# LKS_074DO_0406.net
KiCad netlist of a schematic drawn in Altium Designer
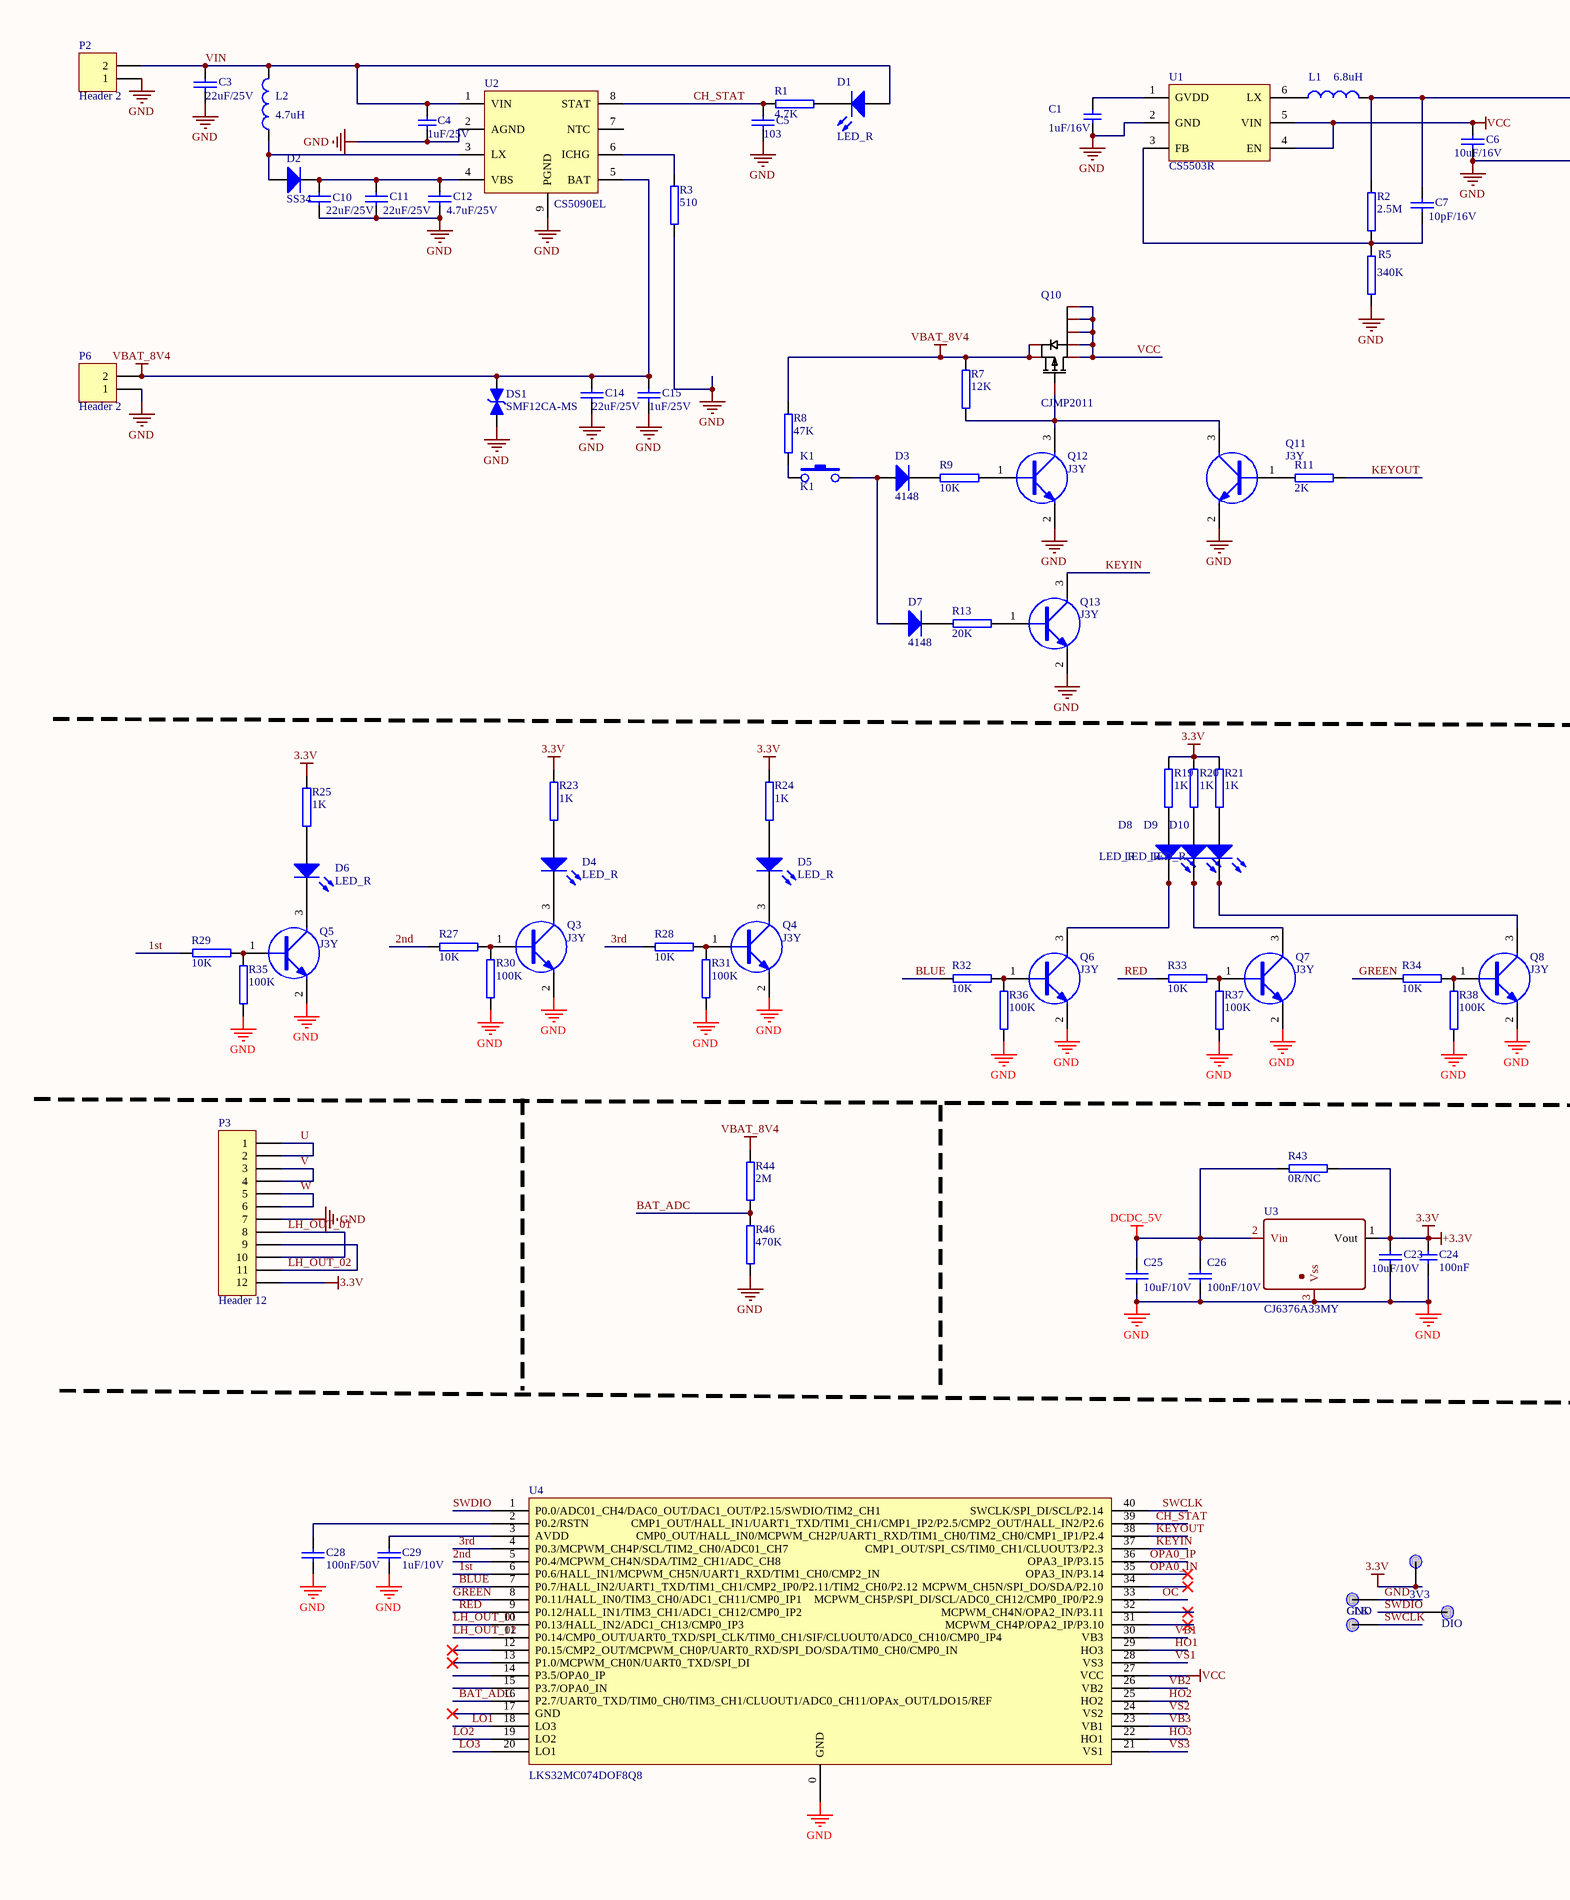
[diagram p0: LKS_074DO_0406.SchDoc, left]
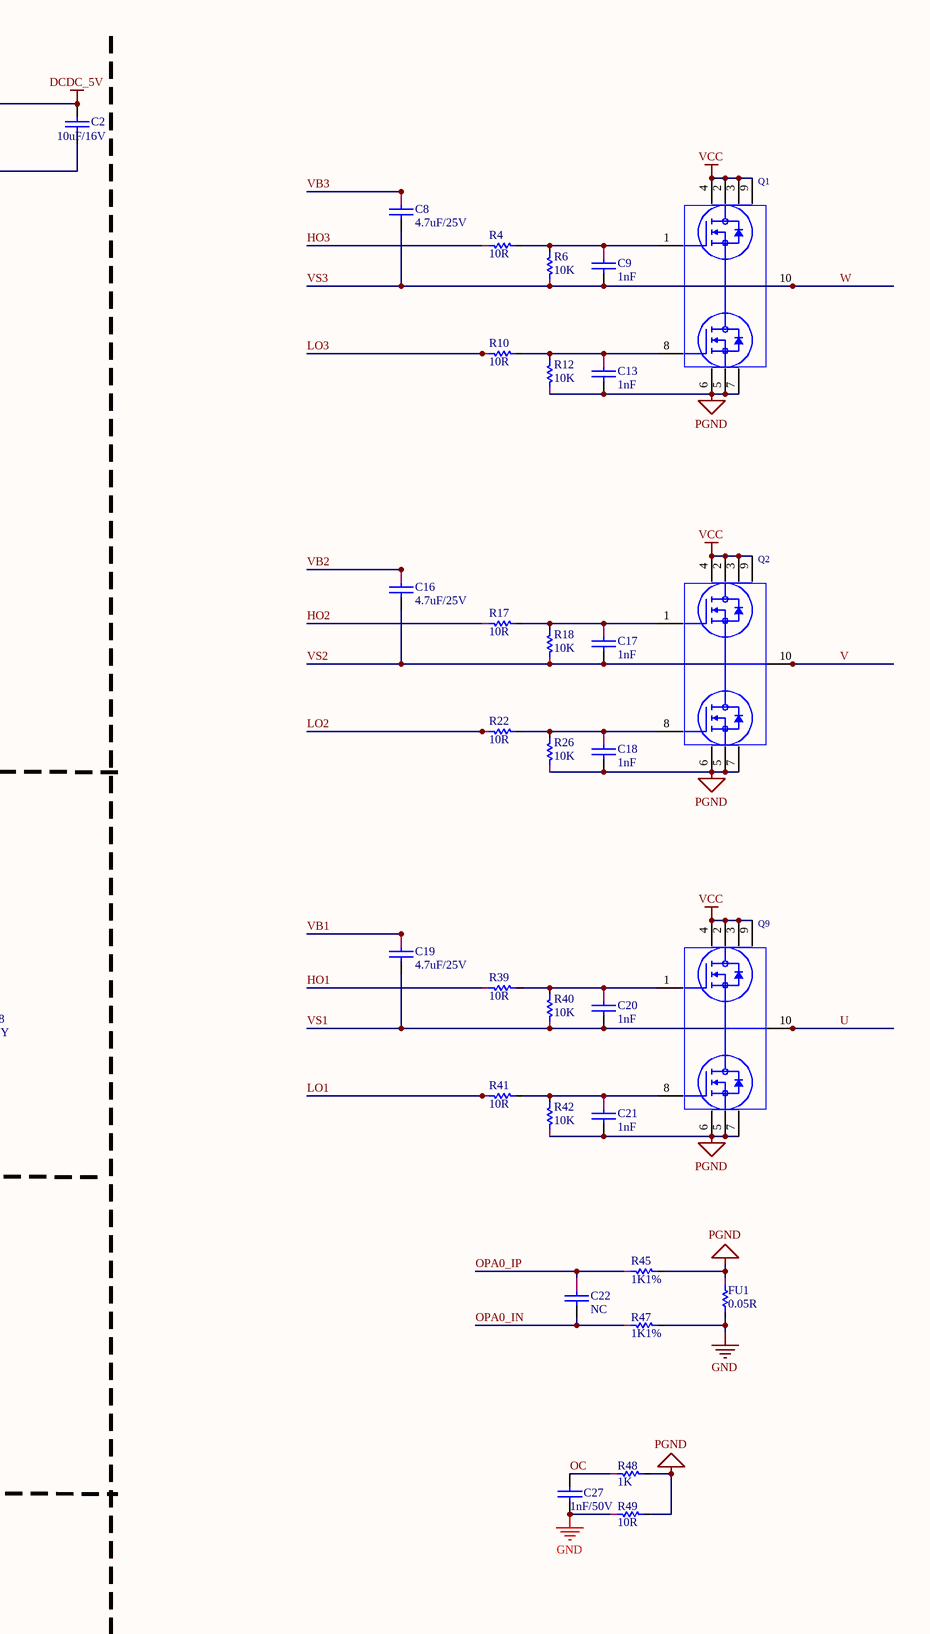
[diagram p1: LKS_074DO_0406.SchDoc, right]

(export (version "E")
  (design (tool "Eeschema 10.0.6"))
  (components
    (comp (ref "3V3") (value "test") (footprint "piot") (libsource (lib "LKS074DO_BRUSH_0329") (part "test")))
    (comp (ref "C1") (value "1uF/16V") (footprint "C 0402_M") (libsource (lib "") (part "CAP_1")))
    (comp (ref "C2")
      (value "10uF/16V")
      (footprint "C 0603_M")
      (description "Capacitor")
      (libsource (lib "*") (part "CAP"))
    )
    (comp (ref "C3")
      (value "22uF/25V")
      (footprint "C 0603_M")
      (description "Capacitor")
      (libsource (lib "*") (part "CAP"))
    )
    (comp (ref "C4") (value "1uF/25V") (footprint "C 0402_M") (libsource (lib "") (part "CAP_1")))
    (comp (ref "C5")
      (value "103")
      (footprint "R 0402_M")
      (description "Capacitor")
      (libsource (lib "*") (part "CAP"))
    )
    (comp (ref "C6")
      (value "10uF/16V")
      (footprint "C 0603_M")
      (description "Capacitor")
      (libsource (lib "*") (part "CAP"))
    )
    (comp (ref "C7")
      (value "10pF/16V")
      (footprint "C 0402_M")
      (description "Capacitor")
      (libsource (lib "*") (part "CAP"))
    )
    (comp (ref "C8")
      (value "4.7uF/25V")
      (footprint "C 0402_M")
      (description "Capacitor")
      (libsource (lib "") (part "CAP_2"))
    )
    (comp (ref "C9")
      (value "1nF")
      (footprint "C 0402_M")
      (description "Capacitor")
      (libsource (lib "") (part "CAP_2"))
    )
    (comp (ref "C10")
      (value "22uF/25V")
      (footprint "C 0603_M")
      (description "Capacitor")
      (libsource (lib "*") (part "CAP"))
    )
    (comp (ref "C11")
      (value "22uF/25V")
      (footprint "C 0603_M")
      (description "Capacitor")
      (libsource (lib "*") (part "CAP"))
    )
    (comp (ref "C12")
      (value "4.7uF/25V")
      (footprint "C 0402_M")
      (description "Capacitor")
      (libsource (lib "*") (part "CAP"))
    )
    (comp (ref "C13")
      (value "1nF")
      (footprint "C 0402_M")
      (description "Capacitor")
      (libsource (lib "") (part "CAP_2"))
    )
    (comp (ref "C14")
      (value "22uF/25V")
      (footprint "C 0603_M")
      (description "Capacitor")
      (libsource (lib "*") (part "CAP"))
    )
    (comp (ref "C15")
      (value "1uF/25V")
      (footprint "C 0402_M")
      (description "Capacitor")
      (libsource (lib "*") (part "CAP"))
    )
    (comp (ref "C16")
      (value "4.7uF/25V")
      (footprint "C 0402_M")
      (description "Capacitor")
      (libsource (lib "") (part "CAP_2"))
    )
    (comp (ref "C17")
      (value "1nF")
      (footprint "C 0402_M")
      (description "Capacitor")
      (libsource (lib "") (part "CAP_2"))
    )
    (comp (ref "C18")
      (value "1nF")
      (footprint "C 0402_M")
      (description "Capacitor")
      (libsource (lib "") (part "CAP_2"))
    )
    (comp (ref "C19")
      (value "4.7uF/25V")
      (footprint "C 0402_M")
      (description "Capacitor")
      (libsource (lib "") (part "CAP_2"))
    )
    (comp (ref "C20")
      (value "1nF")
      (footprint "C 0402_M")
      (description "Capacitor")
      (libsource (lib "") (part "CAP_2"))
    )
    (comp (ref "C21")
      (value "1nF")
      (footprint "C 0402_M")
      (description "Capacitor")
      (libsource (lib "") (part "CAP_2"))
    )
    (comp (ref "C22")
      (value "NC")
      (footprint "C 0402_M")
      (description "Capacitor")
      (libsource (lib "") (part "CAP_2"))
    )
    (comp (ref "C23")
      (value "10uF/10V")
      (footprint "C 0603_M")
      (description "Capacitor")
      (libsource (lib "*") (part "CAP"))
    )
    (comp (ref "C24") (value "100nF") (footprint "C 0402_M") (libsource (lib "") (part "CAP_1")))
    (comp (ref "C25")
      (value "10uF/10V")
      (footprint "C 0603_M")
      (description "Capacitor")
      (libsource (lib "*") (part "CAP"))
    )
    (comp (ref "C26")
      (value "100nF/10V")
      (footprint "C 0402_M")
      (description "Capacitor")
      (libsource (lib "*") (part "CAP"))
    )
    (comp (ref "C27")
      (value "1nF/50V")
      (footprint "C 0402_M")
      (description "Capacitor")
      (libsource (lib "*") (part "C"))
    )
    (comp (ref "C28")
      (value "100nF/50V")
      (footprint "C 0402_M")
      (description "Capacitor")
      (libsource (lib "*") (part "C"))
    )
    (comp (ref "C29")
      (value "1uF/10V")
      (footprint "C 0402_M")
      (description "Capacitor")
      (libsource (lib "*") (part "C"))
    )
    (comp (ref "CLK") (value "test") (footprint "piot") (libsource (lib "LKS074DO_BRUSH_0329") (part "test")))
    (comp (ref "D1") (value "LED_R") (footprint "0603-LED") (libsource (lib "PuXun1") (part "LED")))
    (comp (ref "D2")
      (value "SS34")
      (footprint "SOD123FL")
      (description "Default Diode")
      (fields (field (name "PUBLISHER") "Altium Limited"))
      (libsource (lib "LKS034DO_Motor_0520_1") (part "Diode"))
    )
    (comp (ref "D3")
      (value "4148")
      (footprint "SOD-323")
      (description "Default Diode")
      (fields (field (name "PUBLISHER") "Altium Limited"))
      (libsource (lib "LKS034DO_Motor_0520_1") (part "Diode"))
    )
    (comp (ref "D4") (value "LED_R") (footprint "0603-LED") (libsource (lib "PuXun1") (part "LED")))
    (comp (ref "D5") (value "LED_R") (footprint "0603-LED") (libsource (lib "PuXun1") (part "LED")))
    (comp (ref "D6") (value "LED_R") (footprint "0603-LED") (libsource (lib "PuXun1") (part "LED")))
    (comp (ref "D7")
      (value "4148")
      (footprint "SOD-323")
      (description "Default Diode")
      (fields (field (name "PUBLISHER") "Altium Limited"))
      (libsource (lib "LKS034DO_Motor_0520_1") (part "Diode"))
    )
    (comp (ref "D8") (value "LED_R") (footprint "0603-LED") (libsource (lib "PuXun1") (part "LED")))
    (comp (ref "D9") (value "LED_R") (footprint "0603-LED") (libsource (lib "PuXun1") (part "LED")))
    (comp (ref "D10") (value "LED_R") (footprint "0603-LED") (libsource (lib "PuXun1") (part "LED")))
    (comp (ref "DIO") (value "test") (footprint "piot") (libsource (lib "LKS074DO_BRUSH_0329") (part "test")))
    (comp (ref "DS1")
      (value "SMF12CA-MS")
      (footprint "SOD-123F")
      (description "12V/19.9V")
      (libsource (lib "*") (part "DIODE-3"))
    )
    (comp (ref "FU1") (value "0.05R") (footprint "R 0805_M") (libsource (lib "*") (part "RAS")))
    (comp (ref "GND") (value "test") (footprint "piot") (libsource (lib "LKS074DO_BRUSH_0329") (part "test")))
    (comp (ref "K1") (value "K1") (footprint "SMD3.3X3.3X2") (libsource (lib "SCHLIB_NEW") (part "K1")))
    (comp (ref "L1")
      (value "6.8uH")
      (footprint "SMD3.5X3 .2- duplicate")
      (description "Inductor")
      (fields (field (name "PUBLISHER") "Altium Limited"))
      (libsource (lib "Miscellaneous Devices") (part "Inductor"))
    )
    (comp (ref "L2")
      (value "4.7uH")
      (footprint "SMD3.5X3 .2- duplicate")
      (description "Inductor")
      (fields (field (name "PUBLISHER") "Altium Limited"))
      (libsource (lib "Miscellaneous Devices") (part "Inductor"))
    )
    (comp (ref "P2")
      (value "Header 2")
      (footprint "CONN_SMD_2P_0.6")
      (description "Header, 2-Pin")
      (fields (field (name "PUBLISHER") "Altium Limited"))
      (libsource (lib "Miscellaneous Connectors") (part "Header 2"))
    )
    (comp (ref "P3")
      (value "Header 12")
      (footprint "SMD-12")
      (description "Header, 12-Pin")
      (fields (field (name "PUBLISHER") "Altium Limited"))
      (libsource (lib "Miscellaneous Connectors") (part "Header 12"))
    )
    (comp (ref "P6")
      (value "Header 2")
      (footprint "CONN_SMD_2P_0.6")
      (description "Header, 2-Pin")
      (fields (field (name "PUBLISHER") "Altium Limited"))
      (libsource (lib "Miscellaneous Connectors") (part "Header 2"))
    )
    (comp (ref "Q1") (value "CJBM3020") (footprint "DFN-3X3_8") (libsource (lib "*") (part "CJBM3020")))
    (comp (ref "Q2") (value "CJBM3020") (footprint "DFN-3X3_8") (libsource (lib "*") (part "CJBM3020")))
    (comp (ref "Q3")
      (value "J3Y")
      (footprint "SOT-23")
      (description "NPN Transistor")
      (libsource (lib "*") (part "NPN"))
    )
    (comp (ref "Q4")
      (value "J3Y")
      (footprint "SOT-23")
      (description "NPN Transistor")
      (libsource (lib "*") (part "NPN"))
    )
    (comp (ref "Q5")
      (value "J3Y")
      (footprint "SOT-23")
      (description "NPN Transistor")
      (libsource (lib "*") (part "NPN"))
    )
    (comp (ref "Q6")
      (value "J3Y")
      (footprint "SOT-23")
      (description "NPN Transistor")
      (libsource (lib "*") (part "NPN"))
    )
    (comp (ref "Q7")
      (value "J3Y")
      (footprint "SOT-23")
      (description "NPN Transistor")
      (libsource (lib "*") (part "NPN"))
    )
    (comp (ref "Q8")
      (value "J3Y")
      (footprint "SOT-23")
      (description "NPN Transistor")
      (libsource (lib "*") (part "NPN"))
    )
    (comp (ref "Q9") (value "CJBM3020") (footprint "DFN-3X3_8") (libsource (lib "*") (part "CJBM3020")))
    (comp (ref "Q10")
      (value "CJMP2011")
      (footprint "DFN-6-2X2")
      (libsource (lib "LKS074DO_BRUSH_0329") (part "CJMP2011"))
    )
    (comp (ref "Q11")
      (value "J3Y")
      (footprint "SOT-23")
      (description "NPN Transistor")
      (libsource (lib "*") (part "NPN"))
    )
    (comp (ref "Q12")
      (value "J3Y")
      (footprint "SOT-23")
      (description "NPN Transistor")
      (libsource (lib "*") (part "NPN"))
    )
    (comp (ref "Q13")
      (value "J3Y")
      (footprint "SOT-23")
      (description "NPN Transistor")
      (libsource (lib "*") (part "NPN"))
    )
    (comp (ref "R1") (value "4.7K") (footprint "C 0402_M") (libsource (lib "*") (part "RES2_S")))
    (comp (ref "R2") (value "2.5M") (footprint "C 0402_M") (libsource (lib "*") (part "RES2_S")))
    (comp (ref "R3") (value "510") (footprint "R 0402_M") (libsource (lib "*") (part "RES2_S")))
    (comp (ref "R4") (value "10R") (footprint "R 0402_M") (libsource (lib "*") (part "RAS")))
    (comp (ref "R5") (value "340K") (footprint "C 0402_M") (libsource (lib "*") (part "RES2_S")))
    (comp (ref "R6") (value "10K") (footprint "R 0402_M") (libsource (lib "*") (part "RAS")))
    (comp (ref "R7") (value "12K") (footprint "C 0402_M") (libsource (lib "*") (part "RES2_S")))
    (comp (ref "R8") (value "47K") (footprint "C 0402_M") (libsource (lib "*") (part "RES2_S")))
    (comp (ref "R9") (value "10K") (footprint "C 0402_M") (libsource (lib "*") (part "RES2_S")))
    (comp (ref "R10") (value "10R") (footprint "R 0402_M") (libsource (lib "*") (part "RAS")))
    (comp (ref "R11") (value "2K") (footprint "C 0402_M") (libsource (lib "*") (part "RES2_S")))
    (comp (ref "R12") (value "10K") (footprint "R 0402_M") (libsource (lib "*") (part "RAS")))
    (comp (ref "R13") (value "20K") (footprint "C 0402_M") (libsource (lib "*") (part "RES2_S")))
    (comp (ref "R17") (value "10R") (footprint "R 0402_M") (libsource (lib "*") (part "RAS")))
    (comp (ref "R18") (value "10K") (footprint "R 0402_M") (libsource (lib "*") (part "RAS")))
    (comp (ref "R19") (value "1K") (footprint "C 0402_M") (libsource (lib "*") (part "RES2_S")))
    (comp (ref "R20") (value "1K") (footprint "C 0402_M") (libsource (lib "*") (part "RES2_S")))
    (comp (ref "R21") (value "1K") (footprint "C 0402_M") (libsource (lib "*") (part "RES2_S")))
    (comp (ref "R22") (value "10R") (footprint "R 0402_M") (libsource (lib "*") (part "RAS")))
    (comp (ref "R23") (value "1K") (footprint "C 0402_M") (libsource (lib "*") (part "RES2_S")))
    (comp (ref "R24") (value "1K") (footprint "C 0402_M") (libsource (lib "*") (part "RES2_S")))
    (comp (ref "R25") (value "1K") (footprint "C 0402_M") (libsource (lib "*") (part "RES2_S")))
    (comp (ref "R26") (value "10K") (footprint "R 0402_M") (libsource (lib "*") (part "RAS")))
    (comp (ref "R27") (value "10K") (footprint "C 0402_M") (libsource (lib "*") (part "RES2_S")))
    (comp (ref "R28") (value "10K") (footprint "C 0402_M") (libsource (lib "*") (part "RES2_S")))
    (comp (ref "R29") (value "10K") (footprint "C 0402_M") (libsource (lib "*") (part "RES2_S")))
    (comp (ref "R30") (value "100K") (footprint "C 0402_M") (libsource (lib "*") (part "RES2_S")))
    (comp (ref "R31") (value "100K") (footprint "C 0402_M") (libsource (lib "*") (part "RES2_S")))
    (comp (ref "R32") (value "10K") (footprint "C 0402_M") (libsource (lib "*") (part "RES2_S")))
    (comp (ref "R33") (value "10K") (footprint "C 0402_M") (libsource (lib "*") (part "RES2_S")))
    (comp (ref "R34") (value "10K") (footprint "C 0402_M") (libsource (lib "*") (part "RES2_S")))
    (comp (ref "R35") (value "100K") (footprint "C 0402_M") (libsource (lib "*") (part "RES2_S")))
    (comp (ref "R36") (value "100K") (footprint "C 0402_M") (libsource (lib "*") (part "RES2_S")))
    (comp (ref "R37") (value "100K") (footprint "C 0402_M") (libsource (lib "*") (part "RES2_S")))
    (comp (ref "R38") (value "100K") (footprint "C 0402_M") (libsource (lib "*") (part "RES2_S")))
    (comp (ref "R39") (value "10R") (footprint "R 0402_M") (libsource (lib "*") (part "RAS")))
    (comp (ref "R40") (value "10K") (footprint "R 0402_M") (libsource (lib "*") (part "RAS")))
    (comp (ref "R41") (value "10R") (footprint "R 0402_M") (libsource (lib "*") (part "RAS")))
    (comp (ref "R42") (value "10K") (footprint "R 0402_M") (libsource (lib "*") (part "RAS")))
    (comp (ref "R43") (value "0R/NC") (footprint "0603") (libsource (lib "*") (part "RES2_S")))
    (comp (ref "R44") (value "2M") (footprint "C 0402_M") (libsource (lib "*") (part "RES2_S")))
    (comp (ref "R45") (value "1K1%") (footprint "R 0402_M") (libsource (lib "*") (part "RAS")))
    (comp (ref "R46") (value "470K") (footprint "C 0402_M") (libsource (lib "*") (part "RES2_S")))
    (comp (ref "R47") (value "1K1%") (footprint "R 0402_M") (libsource (lib "*") (part "RAS")))
    (comp (ref "R48") (value "1K") (footprint "R 0402_M") (libsource (lib "*") (part "RAS")))
    (comp (ref "R49") (value "10R") (footprint "R 0402_M") (libsource (lib "*") (part "RAS")))
    (comp (ref "U1")
      (value "CS5503R")
      (footprint "SOT23-6L")
      (libsource (lib "LKS034DO_Motor_0520_1") (part "CS5503R"))
    )
    (comp (ref "U2")
      (value "CS5090EL")
      (footprint "DFN2X2_8_0.5")
      (libsource (lib "LKS034DO_Motor_0520_1") (part "CS5090EL"))
    )
    (comp (ref "U3")
      (value "CJ6376A33MY")
      (footprint "SOT-23")
      (libsource (lib "LKS034DO_Motor_0520_1") (part "78L15"))
    )
    (comp (ref "U4")
      (value "LKS32MC074DOF8Q8")
      (footprint "QFN40")
      (description "芯片")
      (libsource (lib "Q_LINKO_V1.0") (part "LKS32MC074DF8Q8"))
    )
  )
  (nets
    (net (code "1") (name "+3.3V") (class "Default")
      (node (ref "3V3") (pin "1") (pinfunction "1_1") (pintype "passive"))
      (node (ref "C23") (pin "2") (pinfunction "2_2") (pintype "passive"))
      (node (ref "C24") (pin "1") (pinfunction "1_1") (pintype "passive"))
      (node (ref "P3") (pin "12") (pinfunction "12_12") (pintype "passive"))
      (node (ref "R19") (pin "2") (pinfunction "2_2") (pintype "passive"))
      (node (ref "R20") (pin "2") (pinfunction "2_2") (pintype "passive"))
      (node (ref "R21") (pin "2") (pinfunction "2_2") (pintype "passive"))
      (node (ref "R23") (pin "2") (pinfunction "2_2") (pintype "passive"))
      (node (ref "R24") (pin "2") (pinfunction "2_2") (pintype "passive"))
      (node (ref "R25") (pin "2") (pinfunction "2_2") (pintype "passive"))
      (node (ref "R43") (pin "2") (pinfunction "2_2") (pintype "passive"))
      (node (ref "U3") (pin "1") (pinfunction "Vout_1") (pintype "passive"))
    )
    (net (code "2") (name "/1st") (class "Default")
      (node (ref "R29") (pin "2") (pinfunction "2_2") (pintype "passive"))
      (node (ref "U4") (pin "6") (pinfunction "P0.6/HALL_IN1/MCPWM_CH5N/UART1_RXD/TIM1_CH0/CMP2_IN_6") (pintype "passive"))
    )
    (net (code "3") (name "/2nd") (class "Default")
      (node (ref "R27") (pin "2") (pinfunction "2_2") (pintype "passive"))
      (node (ref "U4") (pin "5") (pinfunction "P0.4/MCPWM_CH4N/SDA/TIM2_CH1/ADC_CH8_5") (pintype "passive"))
    )
    (net (code "4") (name "/3rd") (class "Default")
      (node (ref "R28") (pin "2") (pinfunction "2_2") (pintype "passive"))
      (node (ref "U4") (pin "4") (pinfunction "P0.3/MCPWM_CH4P/SCL/TIM2_CH0/ADC01_CH7_4") (pintype "passive"))
    )
    (net (code "5") (name "/BAT_ADC") (class "Default")
      (node (ref "R44") (pin "2") (pinfunction "2_2") (pintype "passive"))
      (node (ref "R46") (pin "1") (pinfunction "1_1") (pintype "passive"))
      (node (ref "U4") (pin "16") (pinfunction "P2.7/UART0_TXD/TIM0_CH0/TIM3_CH1/CLUOUT1/ADC0_CH11/OPAx_OUT/LDO15/REF_16") (pintype "passive"))
    )
    (net (code "6") (name "/BLUE") (class "Default")
      (node (ref "R32") (pin "2") (pinfunction "2_2") (pintype "passive"))
      (node (ref "U4") (pin "7") (pinfunction "P0.7/HALL_IN2/UART1_TXD/TIM1_CH1/CMP2_IP0/P2.11/TIM2_CH0/P2.12_7") (pintype "passive"))
    )
    (net (code "7") (name "/CH_STAT") (class "Default")
      (node (ref "C5") (pin "2") (pinfunction "2_2") (pintype "passive"))
      (node (ref "R1") (pin "1") (pinfunction "1_1") (pintype "passive"))
      (node (ref "U2") (pin "8") (pinfunction "STAT_8") (pintype "passive"))
      (node (ref "U4") (pin "39") (pinfunction "CMP1_OUT/HALL_IN1/UART1_TXD/TIM1_CH1/CMP1_IP2/P2.5/CMP2_OUT/HALL_IN2/P2.6_39") (pintype "passive"))
    )
    (net (code "8") (name "/GREEN") (class "Default")
      (node (ref "R34") (pin "2") (pinfunction "2_2") (pintype "passive"))
      (node (ref "U4") (pin "8") (pinfunction "P0.11/HALL_IN0/TIM3_CH0/ADC1_CH11/CMP0_IP1_8") (pintype "passive"))
    )
    (net (code "9") (name "/HO1") (class "Default")
      (node (ref "R39") (pin "2") (pinfunction "2_2") (pintype "passive"))
      (node (ref "U4") (pin "29") (pinfunction "HO3_29") (pintype "passive"))
    )
    (net (code "10") (name "/HO2") (class "Default")
      (node (ref "R17") (pin "2") (pinfunction "2_2") (pintype "passive"))
      (node (ref "U4") (pin "25") (pinfunction "HO2_25") (pintype "passive"))
    )
    (net (code "11") (name "/HO3") (class "Default")
      (node (ref "R4") (pin "2") (pinfunction "2_2") (pintype "passive"))
      (node (ref "U4") (pin "22") (pinfunction "HO1_22") (pintype "passive"))
    )
    (net (code "12") (name "/KEYIN") (class "Default")
      (node (ref "Q13") (pin "3") (pinfunction "C_3") (pintype "passive"))
      (node (ref "U4") (pin "37") (pinfunction "CMP1_OUT/SPI_CS/TIM0_CH1/CLUOUT3/P2.3_37") (pintype "passive"))
    )
    (net (code "13") (name "/KEYOUT") (class "Default")
      (node (ref "R11") (pin "2") (pinfunction "2_2") (pintype "passive"))
      (node (ref "U4") (pin "38") (pinfunction "CMP0_OUT/HALL_IN0/MCPWM_CH2P/UART1_RXD/TIM1_CH0/TIM2_CH0/CMP1_IP1/P2.4_38") (pintype "passive"))
    )
    (net (code "14") (name "/LH_OUT_01") (class "Default")
      (node (ref "P3") (pin "10") (pinfunction "10_10") (pintype "passive"))
      (node (ref "P3") (pin "8") (pinfunction "8_8") (pintype "passive"))
      (node (ref "U4") (pin "10") (pinfunction "P0.13/HALL_IN2/ADC1_CH13/CMP0_IP3_10") (pintype "passive"))
    )
    (net (code "15") (name "/LH_OUT_02") (class "Default")
      (node (ref "P3") (pin "11") (pinfunction "11_11") (pintype "passive"))
      (node (ref "P3") (pin "9") (pinfunction "9_9") (pintype "passive"))
      (node (ref "U4") (pin "11") (pinfunction "P0.14/CMP0_OUT/UART0_TXD/SPI_CLK/TIM0_CH1/SIF/CLUOUT0/ADC0_CH10/CMP0_IP4_11") (pintype "passive"))
    )
    (net (code "16") (name "/LO1") (class "Default")
      (node (ref "R41") (pin "2") (pinfunction "2_2") (pintype "passive"))
      (node (ref "U4") (pin "18") (pinfunction "LO3_18") (pintype "passive"))
    )
    (net (code "17") (name "/LO2") (class "Default")
      (node (ref "R22") (pin "2") (pinfunction "2_2") (pintype "passive"))
      (node (ref "U4") (pin "19") (pinfunction "LO2_19") (pintype "passive"))
    )
    (net (code "18") (name "/LO3") (class "Default")
      (node (ref "R10") (pin "2") (pinfunction "2_2") (pintype "passive"))
      (node (ref "U4") (pin "20") (pinfunction "LO1_20") (pintype "passive"))
    )
    (net (code "19") (name "/OC") (class "Default")
      (node (ref "C27") (pin "2") (pinfunction "2_2") (pintype "passive"))
      (node (ref "R48") (pin "2") (pinfunction "2_2") (pintype "passive"))
      (node (ref "U4") (pin "33") (pinfunction "MCPWM_CH5P/SPI_DI/SCL/ADC0_CH12/CMP0_IP0/P2.9_33") (pintype "passive"))
    )
    (net (code "20") (name "/OPA0_IN") (class "Default")
      (node (ref "C22") (pin "1") (pinfunction "1_1") (pintype "passive"))
      (node (ref "R47") (pin "2") (pinfunction "2_2") (pintype "passive"))
      (node (ref "U4") (pin "35") (pinfunction "OPA3_IN/P3.14_35") (pintype "passive"))
    )
    (net (code "21") (name "/OPA0_IP") (class "Default")
      (node (ref "C22") (pin "2") (pinfunction "2_2") (pintype "passive"))
      (node (ref "R45") (pin "2") (pinfunction "2_2") (pintype "passive"))
      (node (ref "U4") (pin "36") (pinfunction "OPA3_IP/P3.15_36") (pintype "passive"))
    )
    (net (code "22") (name "/RED") (class "Default")
      (node (ref "R33") (pin "2") (pinfunction "2_2") (pintype "passive"))
      (node (ref "U4") (pin "9") (pinfunction "P0.12/HALL_IN1/TIM3_CH1/ADC1_CH12/CMP0_IP2_9") (pintype "passive"))
    )
    (net (code "23") (name "/SWCLK") (class "Default")
      (node (ref "CLK") (pin "1") (pinfunction "1_1") (pintype "passive"))
      (node (ref "U4") (pin "40") (pinfunction "SWCLK/SPI_DI/SCL/P2.14_40") (pintype "passive"))
    )
    (net (code "24") (name "/SWDIO") (class "Default")
      (node (ref "DIO") (pin "1") (pinfunction "1_1") (pintype "passive"))
      (node (ref "U4") (pin "1") (pinfunction "P0.0/ADC01_CH4/DAC0_OUT/DAC1_OUT/P2.15/SWDIO/TIM2_CH1_1") (pintype "passive"))
    )
    (net (code "25") (name "/U") (class "Default")
      (node (ref "C19") (pin "1") (pinfunction "1_1") (pintype "passive"))
      (node (ref "C20") (pin "1") (pinfunction "1_1") (pintype "passive"))
      (node (ref "P3") (pin "1") (pinfunction "1_1") (pintype "passive"))
      (node (ref "P3") (pin "2") (pinfunction "2_2") (pintype "passive"))
      (node (ref "Q9") (pin "10") (pinfunction "S1/D2_10") (pintype "passive"))
      (node (ref "R40") (pin "2") (pinfunction "2_2") (pintype "passive"))
      (node (ref "U4") (pin "28") (pinfunction "VS3_28") (pintype "passive"))
    )
    (net (code "26") (name "/V") (class "Default")
      (node (ref "C16") (pin "1") (pinfunction "1_1") (pintype "passive"))
      (node (ref "C17") (pin "1") (pinfunction "1_1") (pintype "passive"))
      (node (ref "P3") (pin "3") (pinfunction "3_3") (pintype "passive"))
      (node (ref "P3") (pin "4") (pinfunction "4_4") (pintype "passive"))
      (node (ref "Q2") (pin "10") (pinfunction "S1/D2_10") (pintype "passive"))
      (node (ref "R18") (pin "2") (pinfunction "2_2") (pintype "passive"))
      (node (ref "U4") (pin "24") (pinfunction "VS2_24") (pintype "passive"))
    )
    (net (code "27") (name "/VB1") (class "Default")
      (node (ref "C19") (pin "2") (pinfunction "2_2") (pintype "passive"))
      (node (ref "U4") (pin "30") (pinfunction "VB3_30") (pintype "passive"))
    )
    (net (code "28") (name "/VB2") (class "Default")
      (node (ref "C16") (pin "2") (pinfunction "2_2") (pintype "passive"))
      (node (ref "U4") (pin "26") (pinfunction "VB2_26") (pintype "passive"))
    )
    (net (code "29") (name "/VB3") (class "Default")
      (node (ref "C8") (pin "2") (pinfunction "2_2") (pintype "passive"))
      (node (ref "U4") (pin "23") (pinfunction "VB1_23") (pintype "passive"))
    )
    (net (code "30") (name "/VIN") (class "Default")
      (node (ref "C3") (pin "2") (pinfunction "2_2") (pintype "passive"))
      (node (ref "C4") (pin "1") (pinfunction "1_1") (pintype "passive"))
      (node (ref "D1") (pin "1") (pinfunction "A_1") (pintype "passive"))
      (node (ref "L2") (pin "2") (pinfunction "2_2") (pintype "passive"))
      (node (ref "P2") (pin "2") (pinfunction "2_2") (pintype "passive"))
      (node (ref "U2") (pin "1") (pinfunction "VIN_1") (pintype "passive"))
    )
    (net (code "31") (name "/VS3") (class "Default")
      (node (ref "C8") (pin "1") (pinfunction "1_1") (pintype "passive"))
      (node (ref "C9") (pin "1") (pinfunction "1_1") (pintype "passive"))
      (node (ref "P3") (pin "5") (pinfunction "5_5") (pintype "passive"))
      (node (ref "P3") (pin "6") (pinfunction "6_6") (pintype "passive"))
      (node (ref "Q1") (pin "10") (pinfunction "S1/D2_10") (pintype "passive"))
      (node (ref "R6") (pin "2") (pinfunction "2_2") (pintype "passive"))
      (node (ref "U4") (pin "21") (pinfunction "VS1_21") (pintype "passive"))
    )
    (net (code "32") (name "DCDC_5V") (class "Default")
      (node (ref "C2") (pin "2") (pinfunction "2_2") (pintype "passive"))
      (node (ref "C25") (pin "2") (pinfunction "2_2") (pintype "passive"))
      (node (ref "C26") (pin "1") (pinfunction "1_1") (pintype "passive"))
      (node (ref "C7") (pin "2") (pinfunction "2_2") (pintype "passive"))
      (node (ref "L1") (pin "2") (pinfunction "2_2") (pintype "passive"))
      (node (ref "R2") (pin "1") (pinfunction "1_1") (pintype "passive"))
      (node (ref "R43") (pin "1") (pinfunction "1_1") (pintype "passive"))
      (node (ref "U3") (pin "2") (pinfunction "Vin_2") (pintype "passive"))
    )
    (net (code "33") (name "GND") (class "Default")
      (node (ref "C1") (pin "1") (pinfunction "1_1") (pintype "passive"))
      (node (ref "C10") (pin "1") (pinfunction "1_1") (pintype "passive"))
      (node (ref "C11") (pin "1") (pinfunction "1_1") (pintype "passive"))
      (node (ref "C12") (pin "1") (pinfunction "1_1") (pintype "passive"))
      (node (ref "C14") (pin "1") (pinfunction "1_1") (pintype "passive"))
      (node (ref "C15") (pin "1") (pinfunction "1_1") (pintype "passive"))
      (node (ref "C2") (pin "1") (pinfunction "1_1") (pintype "passive"))
      (node (ref "C23") (pin "1") (pinfunction "1_1") (pintype "passive"))
      (node (ref "C24") (pin "2") (pinfunction "2_2") (pintype "passive"))
      (node (ref "C25") (pin "1") (pinfunction "1_1") (pintype "passive"))
      (node (ref "C26") (pin "2") (pinfunction "2_2") (pintype "passive"))
      (node (ref "C27") (pin "1") (pinfunction "1_1") (pintype "passive"))
      (node (ref "C28") (pin "2") (pinfunction "2_2") (pintype "passive"))
      (node (ref "C29") (pin "1") (pinfunction "1_1") (pintype "passive"))
      (node (ref "C3") (pin "1") (pinfunction "1_1") (pintype "passive"))
      (node (ref "C4") (pin "2") (pinfunction "2_2") (pintype "passive"))
      (node (ref "C5") (pin "1") (pinfunction "1_1") (pintype "passive"))
      (node (ref "C6") (pin "1") (pinfunction "1_1") (pintype "passive"))
      (node (ref "DS1") (pin "2") (pinfunction "K_2") (pintype "passive"))
      (node (ref "FU1") (pin "1") (pinfunction "1_1") (pintype "passive"))
      (node (ref "GND") (pin "1") (pinfunction "1_1") (pintype "passive"))
      (node (ref "P2") (pin "1") (pinfunction "1_1") (pintype "passive"))
      (node (ref "P3") (pin "7") (pinfunction "7_7") (pintype "passive"))
      (node (ref "P6") (pin "1") (pinfunction "1_1") (pintype "passive"))
      (node (ref "Q11") (pin "2") (pinfunction "E_2") (pintype "passive"))
      (node (ref "Q12") (pin "2") (pinfunction "E_2") (pintype "passive"))
      (node (ref "Q13") (pin "2") (pinfunction "E_2") (pintype "passive"))
      (node (ref "Q3") (pin "2") (pinfunction "E_2") (pintype "passive"))
      (node (ref "Q4") (pin "2") (pinfunction "E_2") (pintype "passive"))
      (node (ref "Q5") (pin "2") (pinfunction "E_2") (pintype "passive"))
      (node (ref "Q6") (pin "2") (pinfunction "E_2") (pintype "passive"))
      (node (ref "Q7") (pin "2") (pinfunction "E_2") (pintype "passive"))
      (node (ref "Q8") (pin "2") (pinfunction "E_2") (pintype "passive"))
      (node (ref "R3") (pin "2") (pinfunction "2_2") (pintype "passive"))
      (node (ref "R30") (pin "2") (pinfunction "2_2") (pintype "passive"))
      (node (ref "R31") (pin "2") (pinfunction "2_2") (pintype "passive"))
      (node (ref "R35") (pin "2") (pinfunction "2_2") (pintype "passive"))
      (node (ref "R36") (pin "2") (pinfunction "2_2") (pintype "passive"))
      (node (ref "R37") (pin "2") (pinfunction "2_2") (pintype "passive"))
      (node (ref "R38") (pin "2") (pinfunction "2_2") (pintype "passive"))
      (node (ref "R46") (pin "2") (pinfunction "2_2") (pintype "passive"))
      (node (ref "R47") (pin "1") (pinfunction "1_1") (pintype "passive"))
      (node (ref "R49") (pin "2") (pinfunction "2_2") (pintype "passive"))
      (node (ref "R5") (pin "2") (pinfunction "2_2") (pintype "passive"))
      (node (ref "U1") (pin "2") (pinfunction "GND_2") (pintype "passive"))
      (node (ref "U2") (pin "2") (pinfunction "AGND_2") (pintype "passive"))
      (node (ref "U2") (pin "9") (pinfunction "PGND_9") (pintype "passive"))
      (node (ref "U3") (pin "3") (pinfunction "Vss_3") (pintype "passive"))
      (node (ref "U4") (pin "0") (pinfunction "GND_0") (pintype "passive"))
    )
    (net (code "34") (name "Net-(D1-K)") (class "Default")
      (node (ref "D1") (pin "2") (pinfunction "K_2") (pintype "passive"))
      (node (ref "R1") (pin "2") (pinfunction "2_2") (pintype "passive"))
    )
    (net (code "35") (name "Net-(D2-A)") (class "Default")
      (node (ref "D2") (pin "1") (pinfunction "A_1") (pintype "passive"))
      (node (ref "L2") (pin "1") (pinfunction "1_1") (pintype "passive"))
      (node (ref "U2") (pin "3") (pinfunction "LX_3") (pintype "passive"))
    )
    (net (code "36") (name "Net-(D2-K)") (class "Default")
      (node (ref "C10") (pin "2") (pinfunction "2_2") (pintype "passive"))
      (node (ref "C11") (pin "2") (pinfunction "2_2") (pintype "passive"))
      (node (ref "C12") (pin "2") (pinfunction "2_2") (pintype "passive"))
      (node (ref "D2") (pin "2") (pinfunction "K_2") (pintype "passive"))
      (node (ref "U2") (pin "4") (pinfunction "VBS_4") (pintype "passive"))
    )
    (net (code "37") (name "Net-(D3-A)") (class "Default")
      (node (ref "D3") (pin "1") (pinfunction "A_1") (pintype "passive"))
      (node (ref "D7") (pin "1") (pinfunction "A_1") (pintype "passive"))
      (node (ref "K1") (pin "2") (pintype "passive"))
    )
    (net (code "38") (name "Net-(D3-K)") (class "Default")
      (node (ref "D3") (pin "2") (pinfunction "K_2") (pintype "passive"))
      (node (ref "R9") (pin "1") (pinfunction "1_1") (pintype "passive"))
    )
    (net (code "39") (name "Net-(D4-A)") (class "Default")
      (node (ref "D4") (pin "1") (pinfunction "A_1") (pintype "passive"))
      (node (ref "R23") (pin "1") (pinfunction "1_1") (pintype "passive"))
    )
    (net (code "40") (name "Net-(D4-K)") (class "Default")
      (node (ref "D4") (pin "2") (pinfunction "K_2") (pintype "passive"))
      (node (ref "Q3") (pin "3") (pinfunction "C_3") (pintype "passive"))
    )
    (net (code "41") (name "Net-(D5-A)") (class "Default")
      (node (ref "D5") (pin "1") (pinfunction "A_1") (pintype "passive"))
      (node (ref "R24") (pin "1") (pinfunction "1_1") (pintype "passive"))
    )
    (net (code "42") (name "Net-(D5-K)") (class "Default")
      (node (ref "D5") (pin "2") (pinfunction "K_2") (pintype "passive"))
      (node (ref "Q4") (pin "3") (pinfunction "C_3") (pintype "passive"))
    )
    (net (code "43") (name "Net-(D6-A)") (class "Default")
      (node (ref "D6") (pin "1") (pinfunction "A_1") (pintype "passive"))
      (node (ref "R25") (pin "1") (pinfunction "1_1") (pintype "passive"))
    )
    (net (code "44") (name "Net-(D6-K)") (class "Default")
      (node (ref "D6") (pin "2") (pinfunction "K_2") (pintype "passive"))
      (node (ref "Q5") (pin "3") (pinfunction "C_3") (pintype "passive"))
    )
    (net (code "45") (name "Net-(D7-K)") (class "Default")
      (node (ref "D7") (pin "2") (pinfunction "K_2") (pintype "passive"))
      (node (ref "R13") (pin "1") (pinfunction "1_1") (pintype "passive"))
    )
    (net (code "46") (name "Net-(D8-A)") (class "Default")
      (node (ref "D8") (pin "1") (pinfunction "A_1") (pintype "passive"))
      (node (ref "R19") (pin "1") (pinfunction "1_1") (pintype "passive"))
    )
    (net (code "47") (name "Net-(D8-K)") (class "Default")
      (node (ref "D8") (pin "2") (pinfunction "K_2") (pintype "passive"))
      (node (ref "Q6") (pin "3") (pinfunction "C_3") (pintype "passive"))
    )
    (net (code "48") (name "Net-(D9-A)") (class "Default")
      (node (ref "D9") (pin "1") (pinfunction "A_1") (pintype "passive"))
      (node (ref "R20") (pin "1") (pinfunction "1_1") (pintype "passive"))
    )
    (net (code "49") (name "Net-(D9-K)") (class "Default")
      (node (ref "D9") (pin "2") (pinfunction "K_2") (pintype "passive"))
      (node (ref "Q7") (pin "3") (pinfunction "C_3") (pintype "passive"))
    )
    (net (code "50") (name "Net-(D10-A)") (class "Default")
      (node (ref "D10") (pin "1") (pinfunction "A_1") (pintype "passive"))
      (node (ref "R21") (pin "1") (pinfunction "1_1") (pintype "passive"))
    )
    (net (code "51") (name "Net-(D10-K)") (class "Default")
      (node (ref "D10") (pin "2") (pinfunction "K_2") (pintype "passive"))
      (node (ref "Q8") (pin "3") (pinfunction "C_3") (pintype "passive"))
    )
    (net (code "52") (name "Net-(K1-Pad1)") (class "Default")
      (node (ref "K1") (pin "1") (pintype "passive"))
      (node (ref "R8") (pin "1") (pinfunction "1_1") (pintype "passive"))
    )
    (net (code "53") (name "Net-(Q1-G1)") (class "Default")
      (node (ref "C9") (pin "2") (pinfunction "2_2") (pintype "passive"))
      (node (ref "Q1") (pin "1") (pinfunction "G1_1") (pintype "passive"))
      (node (ref "R4") (pin "1") (pinfunction "1_1") (pintype "passive"))
      (node (ref "R6") (pin "1") (pinfunction "1_1") (pintype "passive"))
    )
    (net (code "54") (name "Net-(Q1-G2)") (class "Default")
      (node (ref "C13") (pin "2") (pinfunction "2_2") (pintype "passive"))
      (node (ref "Q1") (pin "8") (pinfunction "G2_8") (pintype "passive"))
      (node (ref "R10") (pin "1") (pinfunction "1_1") (pintype "passive"))
      (node (ref "R12") (pin "1") (pinfunction "1_1") (pintype "passive"))
    )
    (net (code "55") (name "Net-(Q2-G1)") (class "Default")
      (node (ref "C17") (pin "2") (pinfunction "2_2") (pintype "passive"))
      (node (ref "Q2") (pin "1") (pinfunction "G1_1") (pintype "passive"))
      (node (ref "R17") (pin "1") (pinfunction "1_1") (pintype "passive"))
      (node (ref "R18") (pin "1") (pinfunction "1_1") (pintype "passive"))
    )
    (net (code "56") (name "Net-(Q2-G2)") (class "Default")
      (node (ref "C18") (pin "2") (pinfunction "2_2") (pintype "passive"))
      (node (ref "Q2") (pin "8") (pinfunction "G2_8") (pintype "passive"))
      (node (ref "R22") (pin "1") (pinfunction "1_1") (pintype "passive"))
      (node (ref "R26") (pin "1") (pinfunction "1_1") (pintype "passive"))
    )
    (net (code "57") (name "Net-(Q3-B)") (class "Default")
      (node (ref "Q3") (pin "1") (pinfunction "B_1") (pintype "passive"))
      (node (ref "R27") (pin "1") (pinfunction "1_1") (pintype "passive"))
      (node (ref "R30") (pin "1") (pinfunction "1_1") (pintype "passive"))
    )
    (net (code "58") (name "Net-(Q4-B)") (class "Default")
      (node (ref "Q4") (pin "1") (pinfunction "B_1") (pintype "passive"))
      (node (ref "R28") (pin "1") (pinfunction "1_1") (pintype "passive"))
      (node (ref "R31") (pin "1") (pinfunction "1_1") (pintype "passive"))
    )
    (net (code "59") (name "Net-(Q5-B)") (class "Default")
      (node (ref "Q5") (pin "1") (pinfunction "B_1") (pintype "passive"))
      (node (ref "R29") (pin "1") (pinfunction "1_1") (pintype "passive"))
      (node (ref "R35") (pin "1") (pinfunction "1_1") (pintype "passive"))
    )
    (net (code "60") (name "Net-(Q6-B)") (class "Default")
      (node (ref "Q6") (pin "1") (pinfunction "B_1") (pintype "passive"))
      (node (ref "R32") (pin "1") (pinfunction "1_1") (pintype "passive"))
      (node (ref "R36") (pin "1") (pinfunction "1_1") (pintype "passive"))
    )
    (net (code "61") (name "Net-(Q7-B)") (class "Default")
      (node (ref "Q7") (pin "1") (pinfunction "B_1") (pintype "passive"))
      (node (ref "R33") (pin "1") (pinfunction "1_1") (pintype "passive"))
      (node (ref "R37") (pin "1") (pinfunction "1_1") (pintype "passive"))
    )
    (net (code "62") (name "Net-(Q8-B)") (class "Default")
      (node (ref "Q8") (pin "1") (pinfunction "B_1") (pintype "passive"))
      (node (ref "R34") (pin "1") (pinfunction "1_1") (pintype "passive"))
      (node (ref "R38") (pin "1") (pinfunction "1_1") (pintype "passive"))
    )
    (net (code "63") (name "Net-(Q9-G1)") (class "Default")
      (node (ref "C20") (pin "2") (pinfunction "2_2") (pintype "passive"))
      (node (ref "Q9") (pin "1") (pinfunction "G1_1") (pintype "passive"))
      (node (ref "R39") (pin "1") (pinfunction "1_1") (pintype "passive"))
      (node (ref "R40") (pin "1") (pinfunction "1_1") (pintype "passive"))
    )
    (net (code "64") (name "Net-(Q9-G2)") (class "Default")
      (node (ref "C21") (pin "2") (pinfunction "2_2") (pintype "passive"))
      (node (ref "Q9") (pin "8") (pinfunction "G2_8") (pintype "passive"))
      (node (ref "R41") (pin "1") (pinfunction "1_1") (pintype "passive"))
      (node (ref "R42") (pin "1") (pinfunction "1_1") (pintype "passive"))
    )
    (net (code "65") (name "Net-(Q10-G)") (class "Default")
      (node (ref "Q10") (pin "3") (pinfunction "G_3") (pintype "passive"))
      (node (ref "Q11") (pin "3") (pinfunction "C_3") (pintype "passive"))
      (node (ref "Q12") (pin "3") (pinfunction "C_3") (pintype "passive"))
      (node (ref "R7") (pin "1") (pinfunction "1_1") (pintype "passive"))
    )
    (net (code "66") (name "Net-(Q11-B)") (class "Default")
      (node (ref "Q11") (pin "1") (pinfunction "B_1") (pintype "passive"))
      (node (ref "R11") (pin "1") (pinfunction "1_1") (pintype "passive"))
    )
    (net (code "67") (name "Net-(Q12-B)") (class "Default")
      (node (ref "Q12") (pin "1") (pinfunction "B_1") (pintype "passive"))
      (node (ref "R9") (pin "2") (pinfunction "2_2") (pintype "passive"))
    )
    (net (code "68") (name "Net-(Q13-B)") (class "Default")
      (node (ref "Q13") (pin "1") (pinfunction "B_1") (pintype "passive"))
      (node (ref "R13") (pin "2") (pinfunction "2_2") (pintype "passive"))
    )
    (net (code "69") (name "Net-(U1-FB)") (class "Default")
      (node (ref "C7") (pin "1") (pinfunction "1_1") (pintype "passive"))
      (node (ref "R2") (pin "2") (pinfunction "2_2") (pintype "passive"))
      (node (ref "R5") (pin "1") (pinfunction "1_1") (pintype "passive"))
      (node (ref "U1") (pin "3") (pinfunction "FB_3") (pintype "passive"))
    )
    (net (code "70") (name "Net-(U1-GVDD)") (class "Default")
      (node (ref "C1") (pin "2") (pinfunction "2_2") (pintype "passive"))
      (node (ref "U1") (pin "1") (pinfunction "GVDD_1") (pintype "passive"))
    )
    (net (code "71") (name "Net-(U1-LX)") (class "Default")
      (node (ref "L1") (pin "1") (pinfunction "1_1") (pintype "passive"))
      (node (ref "U1") (pin "6") (pinfunction "LX_6") (pintype "passive"))
    )
    (net (code "72") (name "Net-(U2-ICHG)") (class "Default")
      (node (ref "R3") (pin "1") (pinfunction "1_1") (pintype "passive"))
      (node (ref "U2") (pin "6") (pinfunction "ICHG_6") (pintype "passive"))
    )
    (net (code "73") (name "Net-(U4-AVDD)") (class "Default")
      (node (ref "C29") (pin "2") (pinfunction "2_2") (pintype "passive"))
      (node (ref "U4") (pin "3") (pinfunction "AVDD_3") (pintype "passive"))
    )
    (net (code "74") (name "Net-(U4-P0.2{slash}RSTN)") (class "Default")
      (node (ref "C28") (pin "1") (pinfunction "1_1") (pintype "passive"))
      (node (ref "U4") (pin "2") (pinfunction "P0.2/RSTN_2") (pintype "passive"))
    )
    (net (code "75") (name "PGND") (class "Default")
      (node (ref "C13") (pin "1") (pinfunction "1_1") (pintype "passive"))
      (node (ref "C18") (pin "1") (pinfunction "1_1") (pintype "passive"))
      (node (ref "C21") (pin "1") (pinfunction "1_1") (pintype "passive"))
      (node (ref "FU1") (pin "2") (pinfunction "2_2") (pintype "passive"))
      (node (ref "Q1") (pin "5") (pinfunction "S2_5") (pintype "passive"))
      (node (ref "Q1") (pin "6") (pinfunction "S2_6") (pintype "passive"))
      (node (ref "Q1") (pin "7") (pinfunction "S2_7") (pintype "passive"))
      (node (ref "Q2") (pin "5") (pinfunction "S2_5") (pintype "passive"))
      (node (ref "Q2") (pin "6") (pinfunction "S2_6") (pintype "passive"))
      (node (ref "Q2") (pin "7") (pinfunction "S2_7") (pintype "passive"))
      (node (ref "Q9") (pin "5") (pinfunction "S2_5") (pintype "passive"))
      (node (ref "Q9") (pin "6") (pinfunction "S2_6") (pintype "passive"))
      (node (ref "Q9") (pin "7") (pinfunction "S2_7") (pintype "passive"))
      (node (ref "R12") (pin "2") (pinfunction "2_2") (pintype "passive"))
      (node (ref "R26") (pin "2") (pinfunction "2_2") (pintype "passive"))
      (node (ref "R42") (pin "2") (pinfunction "2_2") (pintype "passive"))
      (node (ref "R45") (pin "1") (pinfunction "1_1") (pintype "passive"))
      (node (ref "R48") (pin "1") (pinfunction "1_1") (pintype "passive"))
      (node (ref "R49") (pin "1") (pinfunction "1_1") (pintype "passive"))
    )
    (net (code "76") (name "VBAT_8V4") (class "Default")
      (node (ref "C14") (pin "2") (pinfunction "2_2") (pintype "passive"))
      (node (ref "C15") (pin "2") (pinfunction "2_2") (pintype "passive"))
      (node (ref "DS1") (pin "1") (pinfunction "A_1") (pintype "passive"))
      (node (ref "P6") (pin "2") (pinfunction "2_2") (pintype "passive"))
      (node (ref "Q10") (pin "4") (pinfunction "S_4") (pintype "passive"))
      (node (ref "Q10") (pin "8") (pinfunction "S_8") (pintype "passive"))
      (node (ref "R44") (pin "1") (pinfunction "1_1") (pintype "passive"))
      (node (ref "R7") (pin "2") (pinfunction "2_2") (pintype "passive"))
      (node (ref "R8") (pin "2") (pinfunction "2_2") (pintype "passive"))
      (node (ref "U2") (pin "5") (pinfunction "BAT_5") (pintype "passive"))
    )
    (net (code "77") (name "VCC") (class "Default")
      (node (ref "C6") (pin "2") (pinfunction "2_2") (pintype "passive"))
      (node (ref "Q1") (pin "2") (pinfunction "D1_2") (pintype "passive"))
      (node (ref "Q1") (pin "3") (pinfunction "D1_3") (pintype "passive"))
      (node (ref "Q1") (pin "4") (pinfunction "D1_4") (pintype "passive"))
      (node (ref "Q1") (pin "9") (pinfunction "D1_9") (pintype "passive"))
      (node (ref "Q10") (pin "1") (pinfunction "D_1") (pintype "passive"))
      (node (ref "Q10") (pin "2") (pinfunction "D_2") (pintype "passive"))
      (node (ref "Q10") (pin "5") (pinfunction "D_5") (pintype "passive"))
      (node (ref "Q10") (pin "6") (pinfunction "D_6") (pintype "passive"))
      (node (ref "Q10") (pin "7") (pinfunction "D_7") (pintype "passive"))
      (node (ref "Q2") (pin "2") (pinfunction "D1_2") (pintype "passive"))
      (node (ref "Q2") (pin "3") (pinfunction "D1_3") (pintype "passive"))
      (node (ref "Q2") (pin "4") (pinfunction "D1_4") (pintype "passive"))
      (node (ref "Q2") (pin "9") (pinfunction "D1_9") (pintype "passive"))
      (node (ref "Q9") (pin "2") (pinfunction "D1_2") (pintype "passive"))
      (node (ref "Q9") (pin "3") (pinfunction "D1_3") (pintype "passive"))
      (node (ref "Q9") (pin "4") (pinfunction "D1_4") (pintype "passive"))
      (node (ref "Q9") (pin "9") (pinfunction "D1_9") (pintype "passive"))
      (node (ref "U1") (pin "4") (pinfunction "EN_4") (pintype "passive"))
      (node (ref "U1") (pin "5") (pinfunction "VIN_5") (pintype "passive"))
      (node (ref "U4") (pin "27") (pinfunction "VCC_27") (pintype "passive"))
    )
    (net (code "78") (name "unconnected-(U2-NTC-Pad7)") (class "Default")
      (node (ref "U2") (pin "7") (pinfunction "NTC_7") (pintype "passive"))
    )
    (net (code "79") (name "unconnected-(U4-GND-Pad17)") (class "Default")
      (node (ref "U4") (pin "17") (pinfunction "GND_17") (pintype "passive+no_connect"))
    )
    (net (code "80") (name "unconnected-(U4-MCPWM_CH4N{slash}OPA2_IN{slash}P3.11-Pad32)") (class "Default")
      (node (ref "U4") (pin "32") (pinfunction "MCPWM_CH4N/OPA2_IN/P3.11_32") (pintype "passive"))
    )
    (net (code "81") (name "unconnected-(U4-MCPWM_CH4P{slash}OPA2_IP{slash}P3.10-Pad31)") (class "Default")
      (node (ref "U4") (pin "31") (pinfunction "MCPWM_CH4P/OPA2_IP/P3.10_31") (pintype "passive"))
    )
    (net (code "82") (name "unconnected-(U4-MCPWM_CH5N{slash}SPI_DO{slash}SDA{slash}P2.10-Pad34)") (class "Default")
      (node (ref "U4") (pin "34") (pinfunction "MCPWM_CH5N/SPI_DO/SDA/P2.10_34") (pintype "passive+no_connect"))
    )
    (net (code "83") (name "unconnected-(U4-P0.15{slash}CMP2_OUT{slash}MCPWM_CH0P{slash}UART0_RXD{slash}SPI_DO{slash}SDA{slash}TIM0_CH0{slash}CMP0_IN-Pad12)") (class "Default")
      (node (ref "U4") (pin "12") (pinfunction "P0.15/CMP2_OUT/MCPWM_CH0P/UART0_RXD/SPI_DO/SDA/TIM0_CH0/CMP0_IN_12") (pintype "passive+no_connect"))
    )
    (net (code "84") (name "unconnected-(U4-P1.0{slash}MCPWM_CH0N{slash}UART0_TXD{slash}SPI_DI-Pad13)") (class "Default")
      (node (ref "U4") (pin "13") (pinfunction "P1.0/MCPWM_CH0N/UART0_TXD/SPI_DI_13") (pintype "passive+no_connect"))
    )
    (net (code "85") (name "unconnected-(U4-P3.5{slash}OPA0_IP-Pad14)") (class "Default")
      (node (ref "U4") (pin "14") (pinfunction "P3.5/OPA0_IP_14") (pintype "passive"))
    )
    (net (code "86") (name "unconnected-(U4-P3.7{slash}OPA0_IN-Pad15)") (class "Default")
      (node (ref "U4") (pin "15") (pinfunction "P3.7/OPA0_IN_15") (pintype "passive"))
    )
  )
)
